# USB_SERIAL_QUAD.net
KiCad netlist of a schematic drawn in Altium Designer
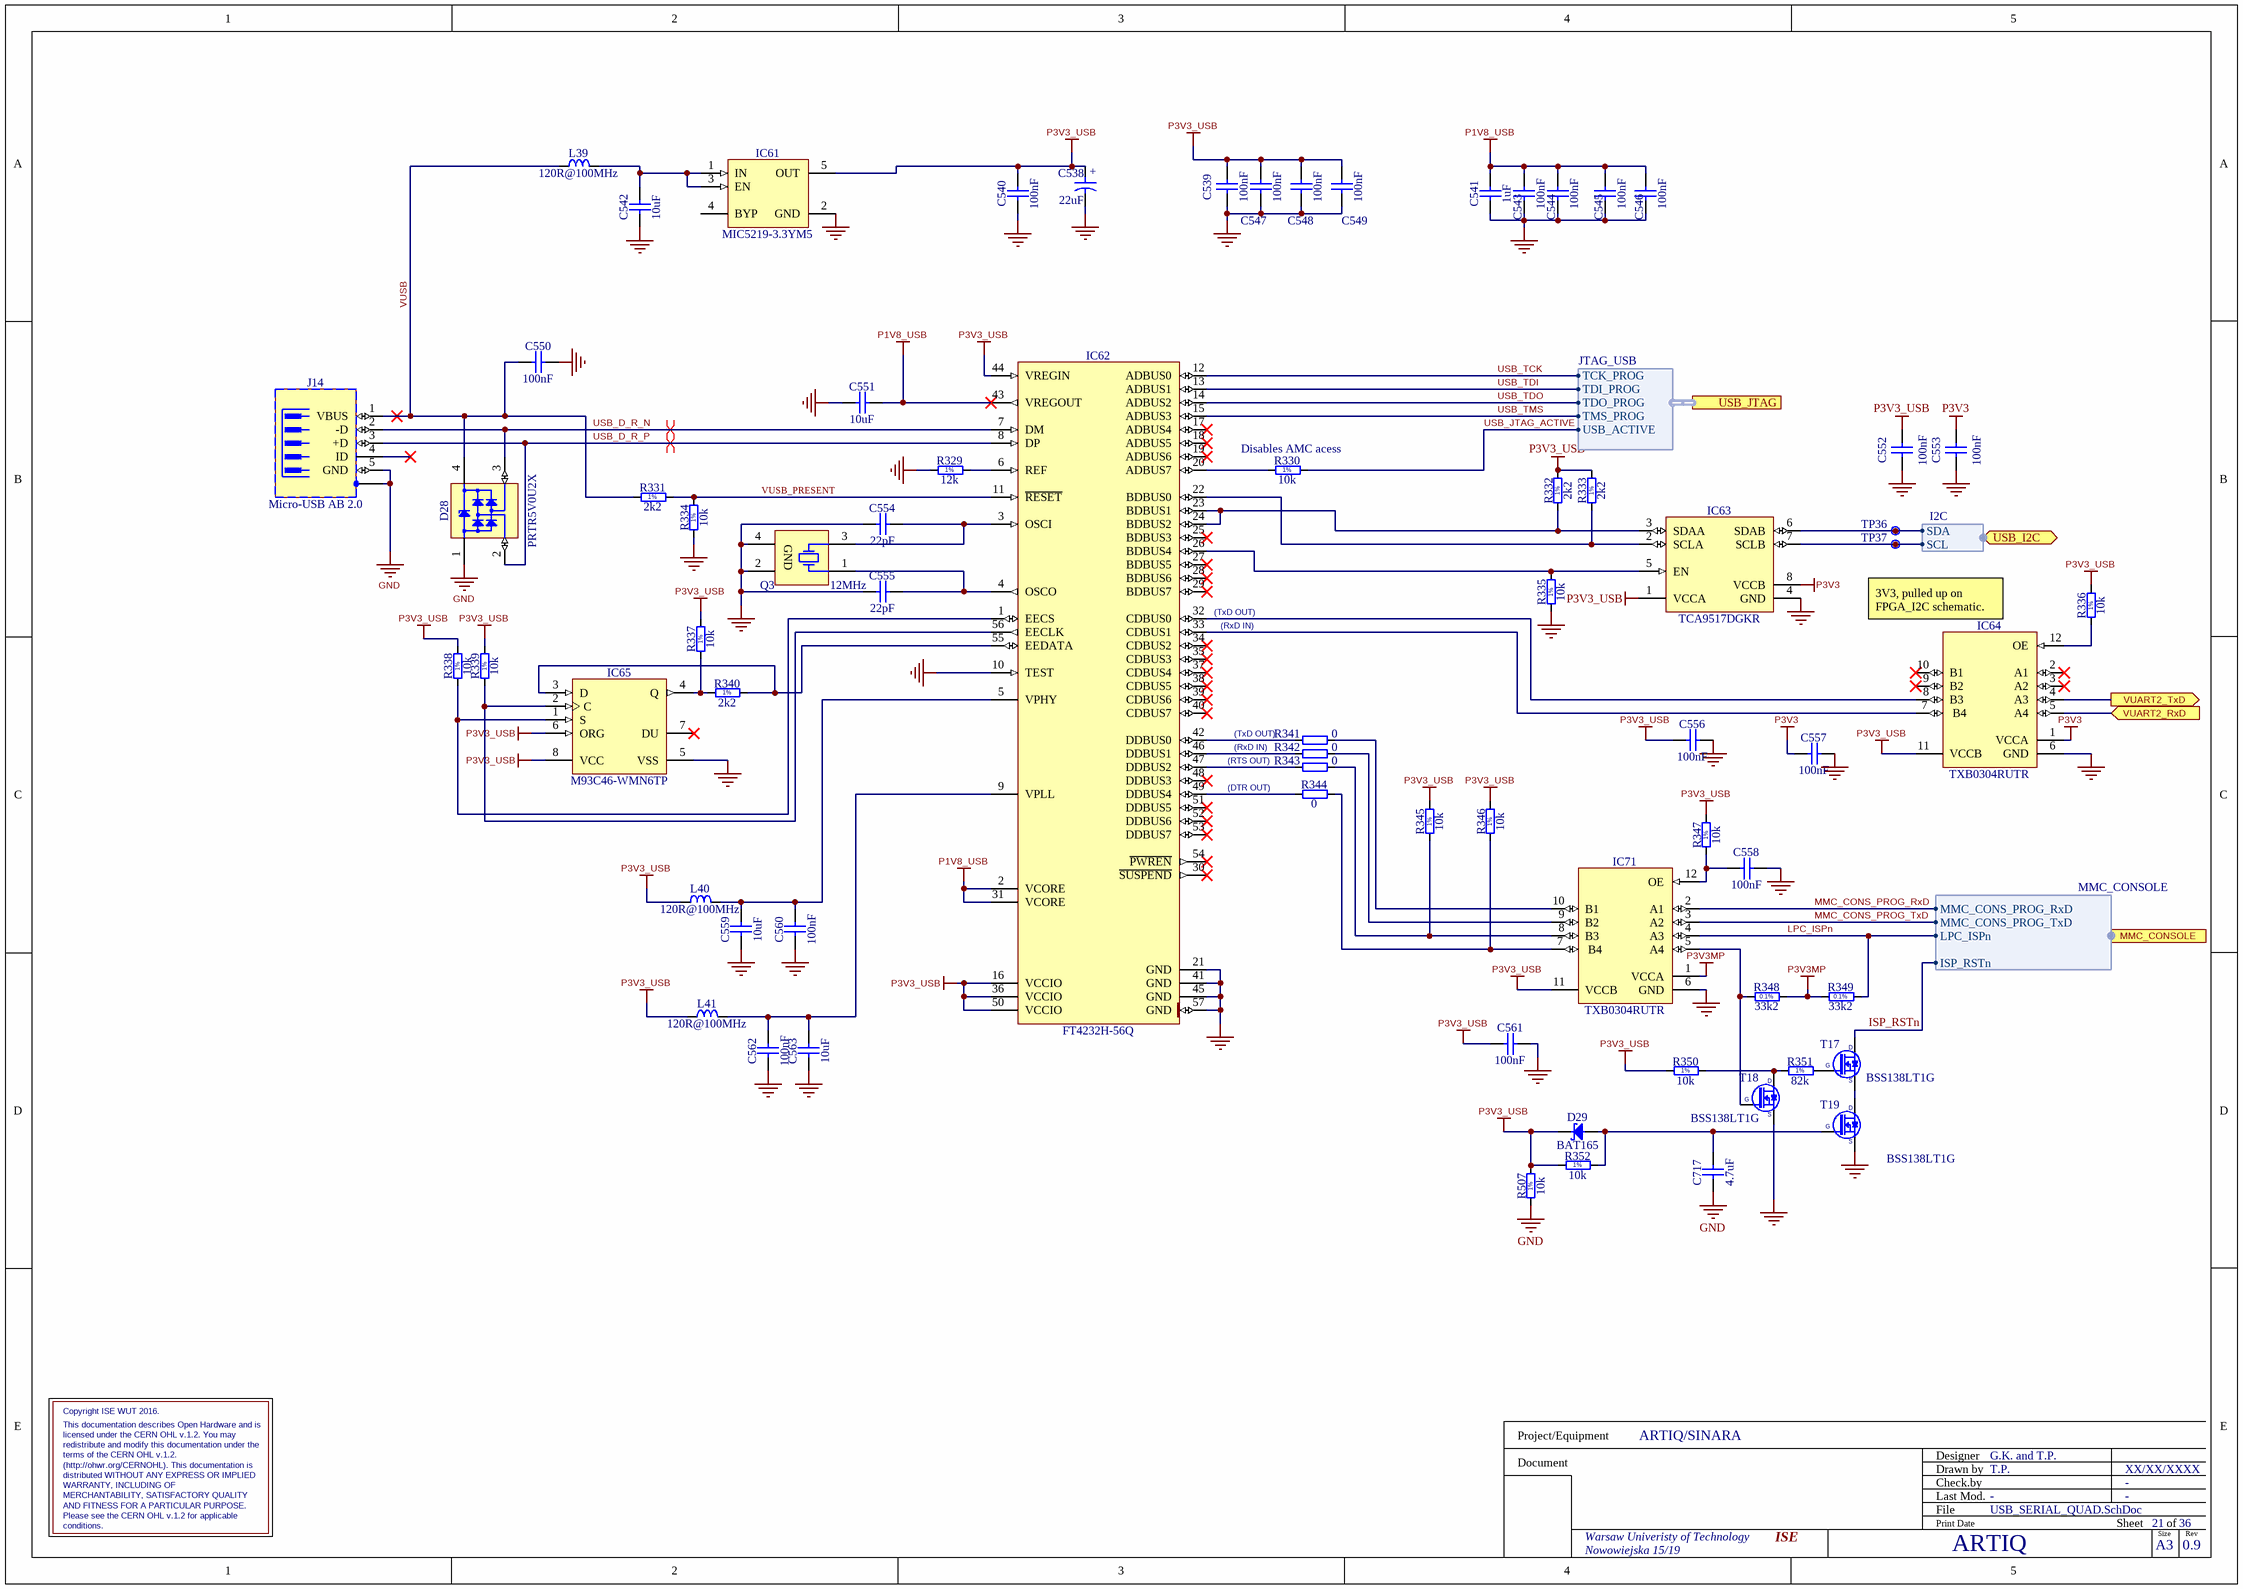
[diagram p0: USB_SERIAL_QUAD.SchDoc]

(export (version "E")
  (design (tool "Eeschema 10.0.6"))
  (components
    (comp (ref "C538")
      (value "22uF")
      (footprint "CAPMP3216X180N")
      (description "Polarised capacitor")
      (fields
        (field (name "MANUFACTURER PART NUMBER") "CTE3216-18_22UF_6.3V_10%_LESR0900")
        (field (name "MANUFACTURER") "GENERIC")
        (field (name "AUTHOR") "CERN DEM JLC")
      )
      (libsource (lib "Capacitors") (part "Capacitor - polarized"))
    )
    (comp (ref "C539")
      (value "100nF")
      (footprint "CAPC0603X33N")
      (description "Non-polarised capacitor")
      (fields
        (field (name "MANUFACTURER PART NUMBER") "CC0201_100NF_6.3V_10%_X5R")
        (field (name "MANUFACTURER") "GENERIC")
        (field (name "AUTHOR") "CERN DEM JLC")
      )
      (libsource (lib "Capacitors") (part "Capacitor - non polarized"))
    )
    (comp (ref "C540")
      (value "100nF")
      (footprint "CAPC0603X33N")
      (description "Non-polarised capacitor")
      (fields
        (field (name "MANUFACTURER PART NUMBER") "CC0201_100NF_6.3V_10%_X5R")
        (field (name "MANUFACTURER") "GENERIC")
        (field (name "AUTHOR") "CERN DEM JLC")
      )
      (libsource (lib "Capacitors") (part "Capacitor - non polarized"))
    )
    (comp (ref "C541")
      (value "1uF")
      (footprint "CAPC1005X55N")
      (description "Non-polarised capacitor")
      (fields
        (field (name "MANUFACTURER PART NUMBER") "CC0402_1UF_16V_10%_X5R")
        (field (name "MANUFACTURER") "GENERIC")
        (field (name "AUTHOR") "CERN DEM JLC")
      )
      (libsource (lib "Capacitors") (part "Capacitor - non polarized"))
    )
    (comp (ref "C542")
      (value "10uF")
      (footprint "CAPC1608X87N")
      (description "Non-polarised capacitor")
      (fields
        (field (name "MANUFACTURER PART NUMBER") "CC0603_10uF_6.3V_20%_X5R")
        (field (name "MANUFACTURER") "GENERIC")
        (field (name "AUTHOR") "CERN DEM JLC")
      )
      (libsource (lib "Capacitors") (part "Capacitor - non polarized"))
    )
    (comp (ref "C543")
      (value "100nF")
      (footprint "CAPC0603X33N")
      (description "Non-polarised capacitor")
      (fields
        (field (name "MANUFACTURER PART NUMBER") "CC0201_100NF_6.3V_10%_X5R")
        (field (name "MANUFACTURER") "GENERIC")
        (field (name "AUTHOR") "CERN DEM JLC")
      )
      (libsource (lib "Capacitors") (part "Capacitor - non polarized"))
    )
    (comp (ref "C544")
      (value "100nF")
      (footprint "CAPC0603X33N")
      (description "Non-polarised capacitor")
      (fields
        (field (name "MANUFACTURER PART NUMBER") "CC0201_100NF_6.3V_10%_X5R")
        (field (name "MANUFACTURER") "GENERIC")
        (field (name "AUTHOR") "CERN DEM JLC")
      )
      (libsource (lib "Capacitors") (part "Capacitor - non polarized"))
    )
    (comp (ref "C545")
      (value "100nF")
      (footprint "CAPC0603X33N")
      (description "Non-polarised capacitor")
      (fields
        (field (name "MANUFACTURER PART NUMBER") "CC0201_100NF_6.3V_10%_X5R")
        (field (name "MANUFACTURER") "GENERIC")
        (field (name "AUTHOR") "CERN DEM JLC")
      )
      (libsource (lib "Capacitors") (part "Capacitor - non polarized"))
    )
    (comp (ref "C546")
      (value "100nF")
      (footprint "CAPC0603X33N")
      (description "Non-polarised capacitor")
      (fields
        (field (name "MANUFACTURER PART NUMBER") "CC0201_100NF_6.3V_10%_X5R")
        (field (name "MANUFACTURER") "GENERIC")
        (field (name "AUTHOR") "CERN DEM JLC")
      )
      (libsource (lib "Capacitors") (part "Capacitor - non polarized"))
    )
    (comp (ref "C547")
      (value "100nF")
      (footprint "CAPC0603X33N")
      (description "Non-polarised capacitor")
      (fields
        (field (name "MANUFACTURER PART NUMBER") "CC0201_100NF_6.3V_10%_X5R")
        (field (name "MANUFACTURER") "GENERIC")
        (field (name "AUTHOR") "CERN DEM JLC")
      )
      (libsource (lib "Capacitors") (part "Capacitor - non polarized"))
    )
    (comp (ref "C548")
      (value "100nF")
      (footprint "CAPC0603X33N")
      (description "Non-polarised capacitor")
      (fields
        (field (name "MANUFACTURER PART NUMBER") "CC0201_100NF_6.3V_10%_X5R")
        (field (name "MANUFACTURER") "GENERIC")
        (field (name "AUTHOR") "CERN DEM JLC")
      )
      (libsource (lib "Capacitors") (part "Capacitor - non polarized"))
    )
    (comp (ref "C549")
      (value "100nF")
      (footprint "CAPC0603X33N")
      (description "Non-polarised capacitor")
      (fields
        (field (name "MANUFACTURER PART NUMBER") "CC0201_100NF_6.3V_10%_X5R")
        (field (name "MANUFACTURER") "GENERIC")
        (field (name "AUTHOR") "CERN DEM JLC")
      )
      (libsource (lib "Capacitors") (part "Capacitor - non polarized"))
    )
    (comp (ref "C550")
      (value "100nF")
      (footprint "CAPC0603X33N")
      (description "Non-polarised capacitor")
      (fields
        (field (name "MANUFACTURER PART NUMBER") "CC0201_100NF_6.3V_10%_X5R")
        (field (name "MANUFACTURER") "GENERIC")
        (field (name "AUTHOR") "CERN DEM JLC")
      )
      (libsource (lib "Capacitors") (part "Capacitor - non polarized"))
    )
    (comp (ref "C551")
      (value "10uF")
      (footprint "CAPC1608X87N")
      (description "Non-polarised capacitor")
      (fields
        (field (name "MANUFACTURER PART NUMBER") "CC0603_10uF_6.3V_20%_X5R")
        (field (name "MANUFACTURER") "GENERIC")
        (field (name "AUTHOR") "CERN DEM JLC")
      )
      (libsource (lib "Capacitors") (part "Capacitor - non polarized"))
    )
    (comp (ref "C552")
      (value "100nF")
      (footprint "CAPC0603X33N")
      (description "Non-polarised capacitor")
      (fields
        (field (name "PART NUMBER") "CC0201_100NF_6.3V_10%_X5R")
        (field (name "VOLTAGE") "6.3V")
        (field (name "AUTHOR") "CERN DEM JLC")
      )
      (libsource (lib "Capacitors") (part "Capacitor - non polarized"))
    )
    (comp (ref "C553")
      (value "100nF")
      (footprint "CAPC0603X33N")
      (description "Non-polarised capacitor")
      (fields
        (field (name "PART NUMBER") "CC0201_100NF_6.3V_10%_X5R")
        (field (name "VOLTAGE") "6.3V")
        (field (name "AUTHOR") "CERN DEM JLC")
      )
      (libsource (lib "Capacitors") (part "Capacitor - non polarized"))
    )
    (comp (ref "C554")
      (value "22pF")
      (footprint "CAPC1005X55N")
      (description "Non-polarised capacitor")
      (fields
        (field (name "MANUFACTURER PART NUMBER") "CC0402_22PF_50V_5%_C0G")
        (field (name "MANUFACTURER") "GENERIC")
        (field (name "AUTHOR") "CERN DEM JLC")
      )
      (libsource (lib "Capacitors") (part "Capacitor - non polarized"))
    )
    (comp (ref "C555")
      (value "22pF")
      (footprint "CAPC1005X55N")
      (description "Non-polarised capacitor")
      (fields
        (field (name "MANUFACTURER PART NUMBER") "CC0402_22PF_50V_5%_C0G")
        (field (name "MANUFACTURER") "GENERIC")
        (field (name "AUTHOR") "CERN DEM JLC")
      )
      (libsource (lib "Capacitors") (part "Capacitor - non polarized"))
    )
    (comp (ref "C556")
      (value "100nF")
      (footprint "CAPC0603X33N")
      (description "Non-polarised capacitor")
      (fields
        (field (name "MANUFACTURER PART NUMBER") "CC0201_100NF_6.3V_10%_X5R")
        (field (name "MANUFACTURER") "GENERIC")
        (field (name "AUTHOR") "CERN DEM JLC")
      )
      (libsource (lib "Capacitors") (part "Capacitor - non polarized"))
    )
    (comp (ref "C557")
      (value "100nF")
      (footprint "CAPC0603X33N")
      (description "Non-polarised capacitor")
      (fields
        (field (name "MANUFACTURER PART NUMBER") "CC0201_100NF_6.3V_10%_X5R")
        (field (name "MANUFACTURER") "GENERIC")
        (field (name "AUTHOR") "CERN DEM JLC")
      )
      (libsource (lib "Capacitors") (part "Capacitor - non polarized"))
    )
    (comp (ref "C558")
      (value "100nF")
      (footprint "CAPC0603X33N")
      (description "Non-polarised capacitor")
      (fields
        (field (name "MANUFACTURER PART NUMBER") "CC0201_100NF_6.3V_10%_X5R")
        (field (name "MANUFACTURER") "GENERIC")
        (field (name "AUTHOR") "CERN DEM JLC")
      )
      (libsource (lib "Capacitors") (part "Capacitor - non polarized"))
    )
    (comp (ref "C559")
      (value "10uF")
      (footprint "CAPC1608X87N")
      (description "Non-polarised capacitor")
      (fields
        (field (name "MANUFACTURER PART NUMBER") "CC0603_10uF_6.3V_20%_X5R")
        (field (name "MANUFACTURER") "GENERIC")
        (field (name "AUTHOR") "CERN DEM JLC")
      )
      (libsource (lib "Capacitors") (part "Capacitor - non polarized"))
    )
    (comp (ref "C560")
      (value "100nF")
      (footprint "CAPC0603X33N")
      (description "Non-polarised capacitor")
      (fields
        (field (name "MANUFACTURER PART NUMBER") "CC0201_100NF_6.3V_10%_X5R")
        (field (name "MANUFACTURER") "GENERIC")
        (field (name "AUTHOR") "CERN DEM JLC")
      )
      (libsource (lib "Capacitors") (part "Capacitor - non polarized"))
    )
    (comp (ref "C561")
      (value "100nF")
      (footprint "CAPC0603X33N")
      (description "Non-polarised capacitor")
      (fields
        (field (name "MANUFACTURER PART NUMBER") "CC0201_100NF_6.3V_10%_X5R")
        (field (name "MANUFACTURER") "GENERIC")
        (field (name "AUTHOR") "CERN DEM JLC")
      )
      (libsource (lib "Capacitors") (part "Capacitor - non polarized"))
    )
    (comp (ref "C562")
      (value "100nF")
      (footprint "CAPC0603X33N")
      (description "Non-polarised capacitor")
      (fields
        (field (name "MANUFACTURER PART NUMBER") "CC0201_100NF_6.3V_10%_X5R")
        (field (name "MANUFACTURER") "GENERIC")
        (field (name "AUTHOR") "CERN DEM JLC")
      )
      (libsource (lib "Capacitors") (part "Capacitor - non polarized"))
    )
    (comp (ref "C563")
      (value "10uF")
      (footprint "CAPC1608X87N")
      (description "Non-polarised capacitor")
      (fields
        (field (name "MANUFACTURER PART NUMBER") "CC0603_10uF_6.3V_20%_X5R")
        (field (name "MANUFACTURER") "GENERIC")
        (field (name "AUTHOR") "CERN DEM JLC")
      )
      (libsource (lib "Capacitors") (part "Capacitor - non polarized"))
    )
    (comp (ref "C717")
      (value "4.7uF")
      (footprint "CAPC1005X55N")
      (description "Non-polarised capacitor")
      (fields
        (field (name "MANUFACTURER PART NUMBER") "CC0402_4.7UF_6.3V_20%_X5R")
        (field (name "MANUFACTURER") "GENERIC")
        (field (name "AUTHOR") "CERN DEM JLC")
      )
      (libsource (lib "Capacitors") (part "Capacitor - non polarized"))
    )
    (comp (ref "D28")
      (value "PRTR5V0U2X")
      (footprint "SOT190P230X110-4N")
      (description "Ultra Low Capacitance Double Rail-to-Rail ESD Protection Diode")
      (fields
        (field (name "MANUFACTURER") "NXP SEMICONDUCTORS")
        (field (name "VOLTAGE") "5.5V")
        (field (name "AUTHOR") "CERN DEM JLC")
      )
      (libsource (lib "ICs And Semiconductors") (part "PRTR5V0U2X"))
    )
    (comp (ref "D29")
      (value "BAT165")
      (footprint "SOD2512X110N")
      (description "Schottky Diode")
      (fields
        (field (name "MANUFACTURER") "INFINEON")
        (field (name "VOLTAGE") "40V")
        (field (name "AUTHOR") "CERN DEM JLC")
      )
      (libsource (lib "ICs And Semiconductors") (part "Diode Schottky"))
    )
    (comp (ref "IC61")
      (value "MIC5219-3.3YM5")
      (footprint "SOT95P280X145-5N")
      (description "500mA Peak Output LDO Regulator")
      (fields (field (name "MANUFACTURER") "MICROCHIP TECHNOLOGY") (field (name "AUTHOR") "CERN DEM WB"))
      (libsource (lib "ICs And Semiconductors") (part "MIC5219-X.XYM5"))
    )
    (comp (ref "IC62")
      (value "FT4232H-56Q")
      (footprint "QFN50P800X800X100-57N-S620")
      (description "Quad High Speed USB to Multipurpose UART/MPSSE IC")
      (fields
        (field (name "MANUFACTURER") "FUTURE TECHNOLOGY DEVICES INTERNATIONAL (FTDI)")
        (field (name "AUTHOR") "CERN DEM JLC")
      )
      (libsource (lib "ICs And Semiconductors") (part "FT4232H-56Q"))
    )
    (comp (ref "IC63")
      (value "TCA9517DGKR")
      (footprint "SOP65P490X110-8N")
      (description "Level-Translating I2C Bus Repeater")
      (fields (field (name "MANUFACTURER") "TEXAS INSTRUMENTS") (field (name "AUTHOR") "CERN DEM JLC"))
      (libsource (lib "ICs And Semiconductors") (part "TCA9517"))
    )
    (comp (ref "IC64")
      (value "TXB0304RUTR")
      (footprint "TEXAS_RUT (R-PUQFN-N12)")
      (description "4-bit Bidirectional Auto-direction Sensing Translator with Fully Symmetric 0.9V to 3.6V Range")
      (fields (field (name "MANUFACTURER") "TEXAS INSTRUMENTS") (field (name "AUTHOR") "CERN DEM JLC"))
      (libsource (lib "ICs And Semiconductors") (part "TXB0304RUTR"))
    )
    (comp (ref "IC65")
      (value "M93C46-WMN6TP")
      (footprint "SOIC127P600X175-8N")
      (description "2.5 to 5.5 V, 1Kb (128x8) Serial Microwire Bus EEPROM")
      (fields (field (name "MANUFACTURER") "ST MICROELECTRONICS") (field (name "AUTHOR") "CERN DEM JLC"))
      (libsource (lib "ICs And Semiconductors") (part "M93C46-WMN6TP"))
    )
    (comp (ref "IC71")
      (value "TXB0304RUTR")
      (footprint "TEXAS_RUT (R-PUQFN-N12)")
      (description "4-bit Bidirectional Auto-direction Sensing Translator with Fully Symmetric 0.9V to 3.6V Range")
      (fields (field (name "MANUFACTURER") "TEXAS INSTRUMENTS") (field (name "AUTHOR") "CERN DEM JLC"))
      (libsource (lib "ICs And Semiconductors") (part "TXB0304RUTR"))
    )
    (comp (ref "J14")
      (value "Micro-USB AB 2.0")
      (footprint "HIROSE_ZX62RD-AB-5P8")
      (description "5 Pin + 1 Shield USB Receptacle")
      (fields
        (field (name "MANUFACTURER PART NUMBER") "ZX62RD-AB-5P8")
        (field (name "MANUFACTURER") "HIROSE (HRS)")
        (field (name "AUTHOR") "CERN DEM JLC")
      )
      (libsource (lib "Connectors") (part "Connector USB 5 Pin + 1Shield"))
    )
    (comp (ref "L39")
      (value "120R@100MHz")
      (footprint "INDC1608X65N")
      (description "Inductor")
      (fields
        (field (name "MANUFACTURER PART NUMBER") "BLM18SG121TN1D")
        (field (name "MANUFACTURER") "MURATA")
        (field (name "AUTHOR") "CERN DEM JLC")
      )
      (libsource (lib "Inductors & Transformers") (part "Inductor"))
    )
    (comp (ref "L40")
      (value "120R@100MHz")
      (footprint "INDC1608X65N")
      (description "Inductor")
      (fields
        (field (name "MANUFACTURER PART NUMBER") "BLM18SG121TN1D")
        (field (name "MANUFACTURER") "MURATA")
        (field (name "AUTHOR") "CERN DEM JLC")
      )
      (libsource (lib "Inductors & Transformers") (part "Inductor"))
    )
    (comp (ref "L41")
      (value "120R@100MHz")
      (footprint "INDC1608X65N")
      (description "Inductor")
      (fields
        (field (name "MANUFACTURER PART NUMBER") "BLM18SG121TN1D")
        (field (name "MANUFACTURER") "MURATA")
        (field (name "AUTHOR") "CERN DEM JLC")
      )
      (libsource (lib "Inductors & Transformers") (part "Inductor"))
    )
    (comp (ref "Q3")
      (value "12MHz")
      (footprint "XTAL_TXC_7M")
      (description "Crystal 4 pins 1=XTAL Control 2=GND3=XTAL 4=GND")
      (fields
        (field (name "MANUFACTURER PART NUMBER") "7M-12.000MAAJ-T")
        (field (name "MANUFACTURER") "TXC CORPORATION")
        (field (name "AUTHOR") "CERN DEM JLC")
      )
      (libsource (lib "ICs And Semiconductors") (part "Quartz Crystal 1X 2GND 3X 4GND"))
    )
    (comp (ref "R329")
      (value "12k")
      (footprint "RESC1005X40N")
      (description "Resistor - 1%")
      (fields
        (field (name "MANUFACTURER PART NUMBER") "R0402_12K_1%_0.0625W_100PPM")
        (field (name "MANUFACTURER") "GENERIC")
        (field (name "AUTHOR") "CERN DEM JLC")
      )
      (libsource (lib "Resistors") (part "Resistor - 1%"))
    )
    (comp (ref "R330")
      (value "10k")
      (footprint "RESC1005X40N")
      (description "Resistor - 1%")
      (fields
        (field (name "MANUFACTURER PART NUMBER") "R0402_10K_1%_0.0625W_100PPM")
        (field (name "MANUFACTURER") "GENERIC")
        (field (name "AUTHOR") "CERN DEM JLC")
      )
      (libsource (lib "Resistors") (part "Resistor - 1%"))
    )
    (comp (ref "R331")
      (value "2k2")
      (footprint "RESC1005X40N")
      (description "Resistor - 1%")
      (fields
        (field (name "MANUFACTURER PART NUMBER") "R0402_2K2_1%_0.0625W_100PPM")
        (field (name "MANUFACTURER") "GENERIC")
        (field (name "AUTHOR") "CERN DEM JLC")
      )
      (libsource (lib "Resistors") (part "Resistor - 1%"))
    )
    (comp (ref "R332")
      (value "2k2")
      (footprint "RESC1005X40N")
      (description "Resistor - 1%")
      (fields
        (field (name "PART NUMBER") "R0402_2K2_1%_0.0625W_100PPM")
        (field (name "POWER") "0.0625W")
        (field (name "AUTHOR") "CERN DEM JLC")
      )
      (libsource (lib "Resistors") (part "Resistor - 1%"))
    )
    (comp (ref "R333")
      (value "2k2")
      (footprint "RESC1005X40N")
      (description "Resistor - 1%")
      (fields
        (field (name "PART NUMBER") "R0402_2K2_1%_0.0625W_100PPM")
        (field (name "POWER") "0.0625W")
        (field (name "AUTHOR") "CERN DEM JLC")
      )
      (libsource (lib "Resistors") (part "Resistor - 1%"))
    )
    (comp (ref "R334")
      (value "10k")
      (footprint "RESC1005X40N")
      (description "Resistor - 1%")
      (fields
        (field (name "MANUFACTURER PART NUMBER") "R0402_10K_1%_0.0625W_100PPM")
        (field (name "MANUFACTURER") "GENERIC")
        (field (name "AUTHOR") "CERN DEM JLC")
      )
      (libsource (lib "Resistors") (part "Resistor - 1%"))
    )
    (comp (ref "R335")
      (value "10k")
      (footprint "RESC1005X40N")
      (description "Resistor - 1%")
      (fields
        (field (name "PART NUMBER") "R0402_10K_1%_0.0625W_100PPM")
        (field (name "POWER") "0.0625W")
        (field (name "AUTHOR") "CERN DEM JLC")
      )
      (libsource (lib "Resistors") (part "Resistor - 1%"))
    )
    (comp (ref "R336")
      (value "10k")
      (footprint "RESC1005X40N")
      (description "Resistor - 1%")
      (fields
        (field (name "MANUFACTURER PART NUMBER") "R0402_10K_1%_0.0625W_100PPM")
        (field (name "MANUFACTURER") "GENERIC")
        (field (name "AUTHOR") "CERN DEM JLC")
      )
      (libsource (lib "Resistors") (part "Resistor - 1%"))
    )
    (comp (ref "R337")
      (value "10k")
      (footprint "RESC1005X40N")
      (description "Resistor - 1%")
      (fields
        (field (name "MANUFACTURER PART NUMBER") "R0402_10K_1%_0.0625W_100PPM")
        (field (name "MANUFACTURER") "GENERIC")
        (field (name "AUTHOR") "CERN DEM JLC")
      )
      (libsource (lib "Resistors") (part "Resistor - 1%"))
    )
    (comp (ref "R338")
      (value "10k")
      (footprint "RESC1005X40N")
      (description "Resistor - 1%")
      (fields
        (field (name "MANUFACTURER PART NUMBER") "R0402_10K_1%_0.0625W_100PPM")
        (field (name "MANUFACTURER") "GENERIC")
        (field (name "AUTHOR") "CERN DEM JLC")
      )
      (libsource (lib "Resistors") (part "Resistor - 1%"))
    )
    (comp (ref "R339")
      (value "10k")
      (footprint "RESC1005X40N")
      (description "Resistor - 1%")
      (fields
        (field (name "MANUFACTURER PART NUMBER") "R0402_10K_1%_0.0625W_100PPM")
        (field (name "MANUFACTURER") "GENERIC")
        (field (name "AUTHOR") "CERN DEM JLC")
      )
      (libsource (lib "Resistors") (part "Resistor - 1%"))
    )
    (comp (ref "R340")
      (value "2k2")
      (footprint "RESC1005X40N")
      (description "Resistor - 1%")
      (fields
        (field (name "MANUFACTURER PART NUMBER") "R0402_2K2_1%_0.0625W_100PPM")
        (field (name "MANUFACTURER") "GENERIC")
        (field (name "AUTHOR") "CERN DEM JLC")
      )
      (libsource (lib "Resistors") (part "Resistor - 1%"))
    )
    (comp (ref "R341")
      (value "0")
      (footprint "RESC1005X40N")
      (description "Resistor")
      (fields
        (field (name "MANUFACTURER PART NUMBER") "R0402_0R_JUMPER")
        (field (name "MANUFACTURER") "GENERIC")
        (field (name "AUTHOR") "CERN DEM JLC")
      )
      (libsource (lib "Resistors") (part "Resistor"))
    )
    (comp (ref "R342")
      (value "0")
      (footprint "RESC1005X40N")
      (description "Resistor")
      (fields
        (field (name "MANUFACTURER PART NUMBER") "R0402_0R_JUMPER")
        (field (name "MANUFACTURER") "GENERIC")
        (field (name "AUTHOR") "CERN DEM JLC")
      )
      (libsource (lib "Resistors") (part "Resistor"))
    )
    (comp (ref "R343")
      (value "0")
      (footprint "RESC1005X40N")
      (description "Resistor")
      (fields
        (field (name "MANUFACTURER PART NUMBER") "R0402_0R_JUMPER")
        (field (name "MANUFACTURER") "GENERIC")
        (field (name "AUTHOR") "CERN DEM JLC")
      )
      (libsource (lib "Resistors") (part "Resistor"))
    )
    (comp (ref "R344")
      (value "0")
      (footprint "RESC1005X40N")
      (description "Resistor")
      (fields
        (field (name "MANUFACTURER PART NUMBER") "R0402_0R_JUMPER")
        (field (name "MANUFACTURER") "GENERIC")
        (field (name "AUTHOR") "CERN DEM JLC")
      )
      (libsource (lib "Resistors") (part "Resistor"))
    )
    (comp (ref "R345")
      (value "10k")
      (footprint "RESC1005X40N")
      (description "Resistor - 1%")
      (fields
        (field (name "MANUFACTURER PART NUMBER") "R0402_10K_1%_0.0625W_100PPM")
        (field (name "MANUFACTURER") "GENERIC")
        (field (name "AUTHOR") "CERN DEM JLC")
      )
      (libsource (lib "Resistors") (part "Resistor - 1%"))
    )
    (comp (ref "R346")
      (value "10k")
      (footprint "RESC1005X40N")
      (description "Resistor - 1%")
      (fields
        (field (name "MANUFACTURER PART NUMBER") "R0402_10K_1%_0.0625W_100PPM")
        (field (name "MANUFACTURER") "GENERIC")
        (field (name "AUTHOR") "CERN DEM JLC")
      )
      (libsource (lib "Resistors") (part "Resistor - 1%"))
    )
    (comp (ref "R347")
      (value "10k")
      (footprint "RESC1005X40N")
      (description "Resistor - 1%")
      (fields
        (field (name "MANUFACTURER PART NUMBER") "R0402_10K_1%_0.0625W_100PPM")
        (field (name "MANUFACTURER") "GENERIC")
        (field (name "AUTHOR") "CERN DEM JLC")
      )
      (libsource (lib "Resistors") (part "Resistor - 1%"))
    )
    (comp (ref "R348")
      (value "33k2")
      (footprint "RESC1608X55N")
      (description "Resistor - 0.1%")
      (fields
        (field (name "MANUFACTURER PART NUMBER") "R0603_33K2_0.1%_0.063W_10PPM")
        (field (name "MANUFACTURER") "GENERIC")
        (field (name "AUTHOR") "CERN DEM JLC")
      )
      (libsource (lib "Resistors") (part "Resistor - 0.1%"))
    )
    (comp (ref "R349")
      (value "33k2")
      (footprint "RESC1608X55N")
      (description "Resistor - 0.1%")
      (fields
        (field (name "MANUFACTURER PART NUMBER") "R0603_33K2_0.1%_0.063W_10PPM")
        (field (name "MANUFACTURER") "GENERIC")
        (field (name "AUTHOR") "CERN DEM JLC")
      )
      (libsource (lib "Resistors") (part "Resistor - 0.1%"))
    )
    (comp (ref "R350")
      (value "10k")
      (footprint "RESC1005X40N")
      (description "Resistor - 1%")
      (fields
        (field (name "MANUFACTURER PART NUMBER") "R0402_10K_1%_0.0625W_100PPM")
        (field (name "MANUFACTURER") "GENERIC")
        (field (name "AUTHOR") "CERN DEM JLC")
      )
      (libsource (lib "Resistors") (part "Resistor - 1%"))
    )
    (comp (ref "R351")
      (value "82k")
      (footprint "RESC1005X40N")
      (description "Resistor - 1%")
      (fields
        (field (name "PART NUMBER") "R0402_82K_1%_0.0625W_100PPM")
        (field (name "POWER") "0.0625W")
        (field (name "AUTHOR") "CERN DEM JLC")
      )
      (libsource (lib "Resistors") (part "Resistor - 1%"))
    )
    (comp (ref "R352")
      (value "10k")
      (footprint "RESC1005X40N")
      (description "Resistor - 1%")
      (fields
        (field (name "MANUFACTURER PART NUMBER") "R0402_10K_1%_0.0625W_100PPM")
        (field (name "MANUFACTURER") "GENERIC")
        (field (name "AUTHOR") "CERN DEM JLC")
      )
      (libsource (lib "Resistors") (part "Resistor - 1%"))
    )
    (comp (ref "R507")
      (value "10k")
      (footprint "RESC1005X40N")
      (description "Resistor - 1%")
      (fields
        (field (name "MANUFACTURER PART NUMBER") "R0402_10K_1%_0.0625W_100PPM")
        (field (name "MANUFACTURER") "GENERIC")
        (field (name "AUTHOR") "CERN DEM JLC")
      )
      (libsource (lib "Resistors") (part "Resistor - 1%"))
    )
    (comp (ref "T17")
      (value "BSS138LT1G")
      (footprint "SOT95P240X110-3N")
      (description "N-CHANNEL MOSFET WITH DIODE")
      (fields (field (name "MANUFACTURER") "ON SEMICONDUCTOR") (field (name "AUTHOR") "CERN DEM JLC"))
      (libsource (lib "ICs And Semiconductors") (part "N-MOSFET-D 1G 2S 3D"))
    )
    (comp (ref "T18")
      (value "BSS138LT1G")
      (footprint "SOT95P240X110-3N")
      (description "N-CHANNEL MOSFET WITH DIODE")
      (fields (field (name "MANUFACTURER") "ON SEMICONDUCTOR") (field (name "AUTHOR") "CERN DEM JLC"))
      (libsource (lib "ICs And Semiconductors") (part "N-MOSFET-D 1G 2S 3D"))
    )
    (comp (ref "T19")
      (value "BSS138LT1G")
      (footprint "SOT95P240X110-3N")
      (description "N-CHANNEL MOSFET WITH DIODE")
      (fields (field (name "MANUFACTURER") "ON SEMICONDUCTOR") (field (name "AUTHOR") "CERN DEM JLC"))
      (libsource (lib "ICs And Semiconductors") (part "N-MOSFET-D 1G 2S 3D"))
    )
    (comp (ref "TP36")
      (value "USB I2C SDA")
      (footprint "TPS127")
      (description "Test Point")
      (fields (field (name "PART NUMBER") "SMD_PAD_1.27X1.27MM") (field (name "AUTHOR") "CERN DEM JLC"))
      (libsource (lib "Eletro-mechanical") (part "Test Point"))
    )
    (comp (ref "TP37")
      (value "USB I2C SCL")
      (footprint "TPS127")
      (description "Test Point")
      (fields (field (name "PART NUMBER") "SMD_PAD_1.27X1.27MM") (field (name "AUTHOR") "CERN DEM JLC"))
      (libsource (lib "Eletro-mechanical") (part "Test Point"))
    )
  )
  (nets
    (net (code "4") (name "/ISP_RSTn") (class "Default")
      (node (ref "T17") (pin "3") (pinfunction "D_3") (pintype "passive"))
    )
    (net (code "5") (name "/LPC_ISPn") (class "Default")
      (node (ref "IC71") (pin "4") (pinfunction "A3_4") (pintype "bidirectional"))
      (node (ref "R349") (pin "1") (pinfunction "1_1") (pintype "passive"))
    )
    (net (code "6") (name "/MMC_CONS_PROG_RxD") (class "Default")
      (node (ref "IC71") (pin "2") (pinfunction "A1_2") (pintype "bidirectional"))
    )
    (net (code "7") (name "/MMC_CONS_PROG_TxD") (class "Default")
      (node (ref "IC71") (pin "3") (pinfunction "A2_3") (pintype "bidirectional"))
    )
    (net (code "8") (name "/USB_D_R_N") (class "Default")
      (node (ref "D28") (pin "3") (pinfunction "I/O2_3") (pintype "bidirectional"))
      (node (ref "IC62") (pin "7") (pinfunction "DM_7") (pintype "input"))
      (node (ref "J14") (pin "2") (pinfunction "-D_2") (pintype "bidirectional"))
    )
    (net (code "9") (name "/USB_D_R_P") (class "Default")
      (node (ref "D28") (pin "2") (pinfunction "I/O1_2") (pintype "bidirectional"))
      (node (ref "IC62") (pin "8") (pinfunction "DP_8") (pintype "input"))
      (node (ref "J14") (pin "3") (pinfunction "+D_3") (pintype "bidirectional"))
    )
    (net (code "10") (name "/USB_JTAG_ACTIVE") (class "Default")
      (node (ref "R330") (pin "1") (pinfunction "1_1") (pintype "passive"))
    )
    (net (code "11") (name "/USB_TCK") (class "Default")
      (node (ref "IC62") (pin "12") (pinfunction "ADBUS0_12") (pintype "bidirectional"))
    )
    (net (code "12") (name "/USB_TDI") (class "Default")
      (node (ref "IC62") (pin "13") (pinfunction "ADBUS1_13") (pintype "bidirectional"))
    )
    (net (code "13") (name "/USB_TDO") (class "Default")
      (node (ref "IC62") (pin "14") (pinfunction "ADBUS2_14") (pintype "bidirectional"))
    )
    (net (code "14") (name "/USB_TMS") (class "Default")
      (node (ref "IC62") (pin "15") (pinfunction "ADBUS3_15") (pintype "bidirectional"))
    )
    (net (code "15") (name "/VUART2_RxD") (class "Default")
      (node (ref "IC64") (pin "5") (pinfunction "A4_5") (pintype "bidirectional"))
    )
    (net (code "16") (name "/VUART2_TxD") (class "Default")
      (node (ref "IC64") (pin "4") (pinfunction "A3_4") (pintype "bidirectional"))
    )
    (net (code "17") (name "/VUSB") (class "Default")
      (node (ref "C550") (pin "2") (pinfunction "2_2") (pintype "passive"))
      (node (ref "D28") (pin "4") (pinfunction "VCC_4") (pintype "power_in"))
      (node (ref "J14") (pin "1") (pinfunction "VBUS_1") (pintype "bidirectional"))
      (node (ref "L39") (pin "1") (pinfunction "1_1") (pintype "passive"))
      (node (ref "R331") (pin "1") (pinfunction "1_1") (pintype "passive"))
    )
    (net (code "18") (name "/VUSB_PRESENT") (class "Default")
      (node (ref "IC62") (pin "11") (pinfunction "~{RESET}_11") (pintype "input"))
      (node (ref "R331") (pin "2") (pinfunction "2_2") (pintype "passive"))
      (node (ref "R334") (pin "2") (pinfunction "2_2") (pintype "passive"))
    )
    (net (code "22") (name "GND") (class "Default")
      (node (ref "C538") (pin "2") (pinfunction "2_2") (pintype "passive"))
      (node (ref "C539") (pin "1") (pinfunction "1_1") (pintype "passive"))
      (node (ref "C540") (pin "1") (pinfunction "1_1") (pintype "passive"))
      (node (ref "C541") (pin "1") (pinfunction "1_1") (pintype "passive"))
      (node (ref "C542") (pin "1") (pinfunction "1_1") (pintype "passive"))
      (node (ref "C543") (pin "1") (pinfunction "1_1") (pintype "passive"))
      (node (ref "C544") (pin "1") (pinfunction "1_1") (pintype "passive"))
      (node (ref "C545") (pin "1") (pinfunction "1_1") (pintype "passive"))
      (node (ref "C546") (pin "1") (pinfunction "1_1") (pintype "passive"))
      (node (ref "C547") (pin "1") (pinfunction "1_1") (pintype "passive"))
      (node (ref "C548") (pin "1") (pinfunction "1_1") (pintype "passive"))
      (node (ref "C549") (pin "1") (pinfunction "1_1") (pintype "passive"))
      (node (ref "C550") (pin "1") (pinfunction "1_1") (pintype "passive"))
      (node (ref "C551") (pin "2") (pinfunction "2_2") (pintype "passive"))
      (node (ref "C552") (pin "1") (pinfunction "1_1") (pintype "passive"))
      (node (ref "C553") (pin "1") (pinfunction "1_1") (pintype "passive"))
      (node (ref "C554") (pin "1") (pinfunction "1_1") (pintype "passive"))
      (node (ref "C555") (pin "1") (pinfunction "1_1") (pintype "passive"))
      (node (ref "C556") (pin "1") (pinfunction "1_1") (pintype "passive"))
      (node (ref "C557") (pin "1") (pinfunction "1_1") (pintype "passive"))
      (node (ref "C558") (pin "1") (pinfunction "1_1") (pintype "passive"))
      (node (ref "C559") (pin "1") (pinfunction "1_1") (pintype "passive"))
      (node (ref "C560") (pin "1") (pinfunction "1_1") (pintype "passive"))
      (node (ref "C561") (pin "1") (pinfunction "1_1") (pintype "passive"))
      (node (ref "C562") (pin "1") (pinfunction "1_1") (pintype "passive"))
      (node (ref "C563") (pin "1") (pinfunction "1_1") (pintype "passive"))
      (node (ref "C717") (pin "1") (pinfunction "1_1") (pintype "passive"))
      (node (ref "D28") (pin "1") (pinfunction "GND_1") (pintype "power_in"))
      (node (ref "IC61") (pin "2") (pinfunction "GND_2") (pintype "power_in"))
      (node (ref "IC62") (pin "10") (pinfunction "TEST_10") (pintype "input"))
      (node (ref "IC62") (pin "21") (pinfunction "GND_21") (pintype "power_in"))
      (node (ref "IC62") (pin "41") (pinfunction "GND_41") (pintype "power_in"))
      (node (ref "IC62") (pin "45") (pinfunction "GND_45") (pintype "power_in"))
      (node (ref "IC62") (pin "57") (pinfunction "GND_57") (pintype "bidirectional"))
      (node (ref "IC63") (pin "4") (pinfunction "GND_4") (pintype "power_in"))
      (node (ref "IC64") (pin "6") (pinfunction "GND_6") (pintype "power_in"))
      (node (ref "IC65") (pin "5") (pinfunction "VSS_5") (pintype "power_in"))
      (node (ref "IC71") (pin "6") (pinfunction "GND_6") (pintype "power_in"))
      (node (ref "J14") (pin "5") (pinfunction "GND_5") (pintype "bidirectional"))
      (node (ref "J14") (pin "6") (pinfunction "SH_6") (pintype "power_in"))
      (node (ref "Q3") (pin "2") (pinfunction "GND_2") (pintype "power_in"))
      (node (ref "Q3") (pin "4") (pinfunction "GND_4") (pintype "power_in"))
      (node (ref "R329") (pin "1") (pinfunction "1_1") (pintype "passive"))
      (node (ref "R334") (pin "1") (pinfunction "1_1") (pintype "passive"))
      (node (ref "R335") (pin "1") (pinfunction "1_1") (pintype "passive"))
      (node (ref "R507") (pin "1") (pinfunction "1_1") (pintype "passive"))
      (node (ref "T18") (pin "2") (pinfunction "S_2") (pintype "passive"))
      (node (ref "T19") (pin "2") (pinfunction "S_2") (pintype "passive"))
    )
    (net (code "23") (name "Net-(D29-A)") (class "Default")
      (node (ref "C717") (pin "2") (pinfunction "2_2") (pintype "passive"))
      (node (ref "D29") (pin "2") (pinfunction "A_2") (pintype "passive"))
      (node (ref "R352") (pin "2") (pinfunction "2_2") (pintype "passive"))
      (node (ref "T19") (pin "1") (pinfunction "G_1") (pintype "passive"))
    )
    (net (code "24") (name "Net-(IC61-EN)") (class "Default")
      (node (ref "C542") (pin "2") (pinfunction "2_2") (pintype "passive"))
      (node (ref "IC61") (pin "1") (pinfunction "IN_1") (pintype "input"))
      (node (ref "IC61") (pin "3") (pinfunction "EN_3") (pintype "input"))
      (node (ref "L39") (pin "2") (pinfunction "2_2") (pintype "passive"))
    )
    (net (code "25") (name "Net-(IC62-ADBUS7)") (class "Default")
      (node (ref "IC62") (pin "20") (pinfunction "ADBUS7_20") (pintype "bidirectional"))
      (node (ref "R330") (pin "2") (pinfunction "2_2") (pintype "passive"))
    )
    (net (code "26") (name "Net-(IC62-BDBUS0)") (class "Default")
      (node (ref "IC62") (pin "22") (pinfunction "BDBUS0_22") (pintype "bidirectional"))
      (node (ref "IC63") (pin "2") (pinfunction "SCLA_2") (pintype "bidirectional"))
      (node (ref "R333") (pin "1") (pinfunction "1_1") (pintype "passive"))
    )
    (net (code "27") (name "Net-(IC62-BDBUS1)") (class "Default")
      (node (ref "IC62") (pin "23") (pinfunction "BDBUS1_23") (pintype "bidirectional"))
      (node (ref "IC62") (pin "24") (pinfunction "BDBUS2_24") (pintype "bidirectional"))
      (node (ref "IC63") (pin "3") (pinfunction "SDAA_3") (pintype "bidirectional"))
      (node (ref "R332") (pin "1") (pinfunction "1_1") (pintype "passive"))
    )
    (net (code "28") (name "Net-(IC62-BDBUS4)") (class "Default")
      (node (ref "IC62") (pin "26") (pinfunction "BDBUS4_26") (pintype "bidirectional"))
      (node (ref "IC63") (pin "5") (pinfunction "EN_5") (pintype "input"))
      (node (ref "R335") (pin "2") (pinfunction "2_2") (pintype "passive"))
    )
    (net (code "29") (name "Net-(IC62-CDBUS0)") (class "Default")
      (node (ref "IC62") (pin "32") (pinfunction "CDBUS0_32") (pintype "bidirectional"))
      (node (ref "IC64") (pin "8") (pinfunction "B3_8") (pintype "bidirectional"))
    )
    (net (code "30") (name "Net-(IC62-CDBUS1)") (class "Default")
      (node (ref "IC62") (pin "33") (pinfunction "CDBUS1_33") (pintype "bidirectional"))
      (node (ref "IC64") (pin "7") (pinfunction "B4_7") (pintype "bidirectional"))
    )
    (net (code "31") (name "Net-(IC62-DDBUS0)") (class "Default")
      (node (ref "IC62") (pin "42") (pinfunction "DDBUS0_42") (pintype "bidirectional"))
      (node (ref "R341") (pin "1") (pinfunction "1_1") (pintype "passive"))
    )
    (net (code "32") (name "Net-(IC62-DDBUS1)") (class "Default")
      (node (ref "IC62") (pin "46") (pinfunction "DDBUS1_46") (pintype "bidirectional"))
      (node (ref "R342") (pin "1") (pinfunction "1_1") (pintype "passive"))
    )
    (net (code "33") (name "Net-(IC62-DDBUS2)") (class "Default")
      (node (ref "IC62") (pin "47") (pinfunction "DDBUS2_47") (pintype "bidirectional"))
      (node (ref "R343") (pin "1") (pinfunction "1_1") (pintype "passive"))
    )
    (net (code "34") (name "Net-(IC62-DDBUS4)") (class "Default")
      (node (ref "IC62") (pin "49") (pinfunction "DDBUS4_49") (pintype "bidirectional"))
      (node (ref "R344") (pin "1") (pinfunction "1_1") (pintype "passive"))
    )
    (net (code "35") (name "Net-(IC62-EECLK)") (class "Default")
      (node (ref "IC62") (pin "56") (pinfunction "EECLK_56") (pintype "output"))
      (node (ref "IC65") (pin "2") (pinfunction "C_2") (pintype "input"))
      (node (ref "R339") (pin "1") (pinfunction "1_1") (pintype "passive"))
    )
    (net (code "36") (name "Net-(IC62-EECS)") (class "Default")
      (node (ref "IC62") (pin "1") (pinfunction "EECS_1") (pintype "bidirectional"))
      (node (ref "IC65") (pin "1") (pinfunction "S_1") (pintype "input"))
      (node (ref "R338") (pin "1") (pinfunction "1_1") (pintype "passive"))
    )
    (net (code "37") (name "Net-(IC62-EEDATA)") (class "Default")
      (node (ref "IC62") (pin "55") (pinfunction "EEDATA_55") (pintype "bidirectional"))
      (node (ref "IC65") (pin "3") (pinfunction "D_3") (pintype "input"))
      (node (ref "R340") (pin "2") (pinfunction "2_2") (pintype "passive"))
    )
    (net (code "38") (name "Net-(IC62-OSCI)") (class "Default")
      (node (ref "C554") (pin "2") (pinfunction "2_2") (pintype "passive"))
      (node (ref "IC62") (pin "3") (pinfunction "OSCI_3") (pintype "input"))
      (node (ref "Q3") (pin "3") (pinfunction "X_3") (pintype "passive"))
    )
    (net (code "39") (name "Net-(IC62-OSCO)") (class "Default")
      (node (ref "C555") (pin "2") (pinfunction "2_2") (pintype "passive"))
      (node (ref "IC62") (pin "4") (pinfunction "OSCO_4") (pintype "output"))
      (node (ref "Q3") (pin "1") (pinfunction "X_1") (pintype "passive"))
    )
    (net (code "40") (name "Net-(IC62-REF)") (class "Default")
      (node (ref "IC62") (pin "6") (pinfunction "REF_6") (pintype "input"))
      (node (ref "R329") (pin "2") (pinfunction "2_2") (pintype "passive"))
    )
    (net (code "41") (name "Net-(IC62-VPHY)") (class "Default")
      (node (ref "C559") (pin "2") (pinfunction "2_2") (pintype "passive"))
      (node (ref "C560") (pin "2") (pinfunction "2_2") (pintype "passive"))
      (node (ref "IC62") (pin "5") (pinfunction "VPHY_5") (pintype "power_in"))
      (node (ref "L40") (pin "2") (pinfunction "2_2") (pintype "passive"))
    )
    (net (code "42") (name "Net-(IC62-VPLL)") (class "Default")
      (node (ref "C562") (pin "2") (pinfunction "2_2") (pintype "passive"))
      (node (ref "C563") (pin "2") (pinfunction "2_2") (pintype "passive"))
      (node (ref "IC62") (pin "9") (pinfunction "VPLL_9") (pintype "power_in"))
      (node (ref "L41") (pin "2") (pinfunction "2_2") (pintype "passive"))
    )
    (net (code "43") (name "Net-(IC63-SCLB)") (class "Default")
      (node (ref "IC63") (pin "7") (pinfunction "SCLB_7") (pintype "bidirectional"))
      (node (ref "TP37") (pin "1") (pinfunction "1_1") (pintype "bidirectional"))
    )
    (net (code "44") (name "Net-(IC63-SDAB)") (class "Default")
      (node (ref "IC63") (pin "6") (pinfunction "SDAB_6") (pintype "bidirectional"))
      (node (ref "TP36") (pin "1") (pinfunction "1_1") (pintype "bidirectional"))
    )
    (net (code "45") (name "Net-(IC64-OE)") (class "Default")
      (node (ref "IC64") (pin "12") (pinfunction "OE_12") (pintype "input"))
      (node (ref "R336") (pin "1") (pinfunction "1_1") (pintype "passive"))
    )
    (net (code "46") (name "Net-(IC65-Q)") (class "Default")
      (node (ref "IC65") (pin "4") (pinfunction "Q_4") (pintype "output"))
      (node (ref "R337") (pin "1") (pinfunction "1_1") (pintype "passive"))
      (node (ref "R340") (pin "1") (pinfunction "1_1") (pintype "passive"))
    )
    (net (code "47") (name "Net-(IC71-A4)") (class "Default")
      (node (ref "IC71") (pin "5") (pinfunction "A4_5") (pintype "bidirectional"))
      (node (ref "R348") (pin "2") (pinfunction "2_2") (pintype "passive"))
      (node (ref "T18") (pin "1") (pinfunction "G_1") (pintype "passive"))
    )
    (net (code "48") (name "Net-(IC71-B1)") (class "Default")
      (node (ref "IC71") (pin "10") (pinfunction "B1_10") (pintype "bidirectional"))
      (node (ref "R341") (pin "2") (pinfunction "2_2") (pintype "passive"))
    )
    (net (code "49") (name "Net-(IC71-B2)") (class "Default")
      (node (ref "IC71") (pin "9") (pinfunction "B2_9") (pintype "bidirectional"))
      (node (ref "R342") (pin "2") (pinfunction "2_2") (pintype "passive"))
    )
    (net (code "50") (name "Net-(IC71-B3)") (class "Default")
      (node (ref "IC71") (pin "8") (pinfunction "B3_8") (pintype "bidirectional"))
      (node (ref "R343") (pin "2") (pinfunction "2_2") (pintype "passive"))
      (node (ref "R345") (pin "1") (pinfunction "1_1") (pintype "passive"))
    )
    (net (code "51") (name "Net-(IC71-B4)") (class "Default")
      (node (ref "IC71") (pin "7") (pinfunction "B4_7") (pintype "bidirectional"))
      (node (ref "R344") (pin "2") (pinfunction "2_2") (pintype "passive"))
      (node (ref "R346") (pin "1") (pinfunction "1_1") (pintype "passive"))
    )
    (net (code "52") (name "Net-(IC71-OE)") (class "Default")
      (node (ref "C558") (pin "2") (pinfunction "2_2") (pintype "passive"))
      (node (ref "IC71") (pin "12") (pinfunction "OE_12") (pintype "input"))
      (node (ref "R347") (pin "1") (pinfunction "1_1") (pintype "passive"))
    )
    (net (code "53") (name "Net-(T17-G)") (class "Default")
      (node (ref "R351") (pin "2") (pinfunction "2_2") (pintype "passive"))
      (node (ref "T17") (pin "1") (pinfunction "G_1") (pintype "passive"))
    )
    (net (code "54") (name "Net-(T17-S)") (class "Default")
      (node (ref "T17") (pin "2") (pinfunction "S_2") (pintype "passive"))
      (node (ref "T19") (pin "3") (pinfunction "D_3") (pintype "passive"))
    )
    (net (code "55") (name "Net-(T18-D)") (class "Default")
      (node (ref "R350") (pin "2") (pinfunction "2_2") (pintype "passive"))
      (node (ref "R351") (pin "1") (pinfunction "1_1") (pintype "passive"))
      (node (ref "T18") (pin "3") (pinfunction "D_3") (pintype "passive"))
    )
    (net (code "56") (name "P1V8_USB") (class "Default")
      (node (ref "C541") (pin "2") (pinfunction "2_2") (pintype "passive"))
      (node (ref "C543") (pin "2") (pinfunction "2_2") (pintype "passive"))
      (node (ref "C544") (pin "2") (pinfunction "2_2") (pintype "passive"))
      (node (ref "C545") (pin "2") (pinfunction "2_2") (pintype "passive"))
      (node (ref "C546") (pin "2") (pinfunction "2_2") (pintype "passive"))
      (node (ref "C551") (pin "1") (pinfunction "1_1") (pintype "passive"))
      (node (ref "IC62") (pin "2") (pinfunction "VCORE_2") (pintype "power_in"))
      (node (ref "IC62") (pin "31") (pinfunction "VCORE_31") (pintype "power_in"))
      (node (ref "IC62") (pin "43") (pinfunction "VREGOUT_43") (pintype "output"))
    )
    (net (code "57") (name "P3V3") (class "Default")
      (node (ref "C553") (pin "2") (pinfunction "2_2") (pintype "passive"))
      (node (ref "C557") (pin "2") (pinfunction "2_2") (pintype "passive"))
      (node (ref "IC63") (pin "8") (pinfunction "VCCB_8") (pintype "power_in"))
      (node (ref "IC64") (pin "1") (pinfunction "VCCA_1") (pintype "power_in"))
    )
    (net (code "58") (name "P3V3MP") (class "Default")
      (node (ref "IC71") (pin "1") (pinfunction "VCCA_1") (pintype "power_in"))
      (node (ref "R348") (pin "1") (pinfunction "1_1") (pintype "passive"))
      (node (ref "R349") (pin "2") (pinfunction "2_2") (pintype "passive"))
    )
    (net (code "59") (name "P3V3_USB") (class "Default")
      (node (ref "C538") (pin "1") (pinfunction "1_1") (pintype "passive"))
      (node (ref "C539") (pin "2") (pinfunction "2_2") (pintype "passive"))
      (node (ref "C540") (pin "2") (pinfunction "2_2") (pintype "passive"))
      (node (ref "C547") (pin "2") (pinfunction "2_2") (pintype "passive"))
      (node (ref "C548") (pin "2") (pinfunction "2_2") (pintype "passive"))
      (node (ref "C549") (pin "2") (pinfunction "2_2") (pintype "passive"))
      (node (ref "C552") (pin "2") (pinfunction "2_2") (pintype "passive"))
      (node (ref "C556") (pin "2") (pinfunction "2_2") (pintype "passive"))
      (node (ref "C561") (pin "2") (pinfunction "2_2") (pintype "passive"))
      (node (ref "D29") (pin "1") (pinfunction "C_1") (pintype "passive"))
      (node (ref "IC61") (pin "5") (pinfunction "OUT_5") (pintype "power_in"))
      (node (ref "IC62") (pin "16") (pinfunction "VCCIO_16") (pintype "power_in"))
      (node (ref "IC62") (pin "36") (pinfunction "VCCIO_36") (pintype "power_in"))
      (node (ref "IC62") (pin "44") (pinfunction "VREGIN_44") (pintype "input"))
      (node (ref "IC62") (pin "50") (pinfunction "VCCIO_50") (pintype "power_in"))
      (node (ref "IC63") (pin "1") (pinfunction "VCCA_1") (pintype "power_in"))
      (node (ref "IC64") (pin "11") (pinfunction "VCCB_11") (pintype "power_in"))
      (node (ref "IC65") (pin "6") (pinfunction "ORG_6") (pintype "input"))
      (node (ref "IC65") (pin "8") (pinfunction "VCC_8") (pintype "power_in"))
      (node (ref "IC71") (pin "11") (pinfunction "VCCB_11") (pintype "power_in"))
      (node (ref "L40") (pin "1") (pinfunction "1_1") (pintype "passive"))
      (node (ref "L41") (pin "1") (pinfunction "1_1") (pintype "passive"))
      (node (ref "R332") (pin "2") (pinfunction "2_2") (pintype "passive"))
      (node (ref "R333") (pin "2") (pinfunction "2_2") (pintype "passive"))
      (node (ref "R336") (pin "2") (pinfunction "2_2") (pintype "passive"))
      (node (ref "R337") (pin "2") (pinfunction "2_2") (pintype "passive"))
      (node (ref "R338") (pin "2") (pinfunction "2_2") (pintype "passive"))
      (node (ref "R339") (pin "2") (pinfunction "2_2") (pintype "passive"))
      (node (ref "R345") (pin "2") (pinfunction "2_2") (pintype "passive"))
      (node (ref "R346") (pin "2") (pinfunction "2_2") (pintype "passive"))
      (node (ref "R347") (pin "2") (pinfunction "2_2") (pintype "passive"))
      (node (ref "R350") (pin "1") (pinfunction "1_1") (pintype "passive"))
      (node (ref "R352") (pin "1") (pinfunction "1_1") (pintype "passive"))
      (node (ref "R507") (pin "2") (pinfunction "2_2") (pintype "passive"))
    )
    (net (code "60") (name "unconnected-(IC61-BYP-Pad4)") (class "Default")
      (node (ref "IC61") (pin "4") (pinfunction "BYP_4") (pintype "passive"))
    )
    (net (code "61") (name "unconnected-(IC62-ADBUS4-Pad17)") (class "Default")
      (node (ref "IC62") (pin "17") (pinfunction "ADBUS4_17") (pintype "bidirectional+no_connect"))
    )
    (net (code "62") (name "unconnected-(IC62-ADBUS5-Pad18)") (class "Default")
      (node (ref "IC62") (pin "18") (pinfunction "ADBUS5_18") (pintype "bidirectional+no_connect"))
    )
    (net (code "63") (name "unconnected-(IC62-ADBUS6-Pad19)") (class "Default")
      (node (ref "IC62") (pin "19") (pinfunction "ADBUS6_19") (pintype "bidirectional+no_connect"))
    )
    (net (code "64") (name "unconnected-(IC62-BDBUS3-Pad25)") (class "Default")
      (node (ref "IC62") (pin "25") (pinfunction "BDBUS3_25") (pintype "bidirectional+no_connect"))
    )
    (net (code "65") (name "unconnected-(IC62-BDBUS5-Pad27)") (class "Default")
      (node (ref "IC62") (pin "27") (pinfunction "BDBUS5_27") (pintype "bidirectional+no_connect"))
    )
    (net (code "66") (name "unconnected-(IC62-BDBUS6-Pad28)") (class "Default")
      (node (ref "IC62") (pin "28") (pinfunction "BDBUS6_28") (pintype "bidirectional+no_connect"))
    )
    (net (code "67") (name "unconnected-(IC62-BDBUS7-Pad29)") (class "Default")
      (node (ref "IC62") (pin "29") (pinfunction "BDBUS7_29") (pintype "bidirectional+no_connect"))
    )
    (net (code "68") (name "unconnected-(IC62-CDBUS2-Pad34)") (class "Default")
      (node (ref "IC62") (pin "34") (pinfunction "CDBUS2_34") (pintype "bidirectional+no_connect"))
    )
    (net (code "69") (name "unconnected-(IC62-CDBUS3-Pad35)") (class "Default")
      (node (ref "IC62") (pin "35") (pinfunction "CDBUS3_35") (pintype "bidirectional+no_connect"))
    )
    (net (code "70") (name "unconnected-(IC62-CDBUS4-Pad37)") (class "Default")
      (node (ref "IC62") (pin "37") (pinfunction "CDBUS4_37") (pintype "bidirectional+no_connect"))
    )
    (net (code "71") (name "unconnected-(IC62-CDBUS5-Pad38)") (class "Default")
      (node (ref "IC62") (pin "38") (pinfunction "CDBUS5_38") (pintype "bidirectional+no_connect"))
    )
    (net (code "72") (name "unconnected-(IC62-CDBUS6-Pad39)") (class "Default")
      (node (ref "IC62") (pin "39") (pinfunction "CDBUS6_39") (pintype "bidirectional+no_connect"))
    )
    (net (code "73") (name "unconnected-(IC62-CDBUS7-Pad40)") (class "Default")
      (node (ref "IC62") (pin "40") (pinfunction "CDBUS7_40") (pintype "bidirectional+no_connect"))
    )
    (net (code "74") (name "unconnected-(IC62-DDBUS3-Pad48)") (class "Default")
      (node (ref "IC62") (pin "48") (pinfunction "DDBUS3_48") (pintype "bidirectional+no_connect"))
    )
    (net (code "75") (name "unconnected-(IC62-DDBUS5-Pad51)") (class "Default")
      (node (ref "IC62") (pin "51") (pinfunction "DDBUS5_51") (pintype "bidirectional+no_connect"))
    )
    (net (code "76") (name "unconnected-(IC62-DDBUS6-Pad52)") (class "Default")
      (node (ref "IC62") (pin "52") (pinfunction "DDBUS6_52") (pintype "bidirectional+no_connect"))
    )
    (net (code "77") (name "unconnected-(IC62-DDBUS7-Pad53)") (class "Default")
      (node (ref "IC62") (pin "53") (pinfunction "DDBUS7_53") (pintype "bidirectional+no_connect"))
    )
    (net (code "78") (name "unconnected-(IC62-~{PWREN}-Pad54)") (class "Default")
      (node (ref "IC62") (pin "54") (pinfunction "~{PWREN}_54") (pintype "output+no_connect"))
    )
    (net (code "79") (name "unconnected-(IC62-~{SUSPEND}-Pad30)") (class "Default")
      (node (ref "IC62") (pin "30") (pinfunction "~{SUSPEND}_30") (pintype "output+no_connect"))
    )
    (net (code "80") (name "unconnected-(IC64-A1-Pad2)") (class "Default")
      (node (ref "IC64") (pin "2") (pinfunction "A1_2") (pintype "bidirectional+no_connect"))
    )
    (net (code "81") (name "unconnected-(IC64-A2-Pad3)") (class "Default")
      (node (ref "IC64") (pin "3") (pinfunction "A2_3") (pintype "bidirectional+no_connect"))
    )
    (net (code "82") (name "unconnected-(IC64-B1-Pad10)") (class "Default")
      (node (ref "IC64") (pin "10") (pinfunction "B1_10") (pintype "bidirectional+no_connect"))
    )
    (net (code "83") (name "unconnected-(IC64-B2-Pad9)") (class "Default")
      (node (ref "IC64") (pin "9") (pinfunction "B2_9") (pintype "bidirectional+no_connect"))
    )
    (net (code "84") (name "unconnected-(IC65-DU-Pad7)") (class "Default")
      (node (ref "IC65") (pin "7") (pinfunction "DU_7") (pintype "passive+no_connect"))
    )
    (net (code "85") (name "unconnected-(J14-ID-Pad4)") (class "Default")
      (node (ref "J14") (pin "4") (pinfunction "ID_4") (pintype "passive+no_connect"))
    )
  )
)
